# quadcopter.net
KiCad netlist of a schematic drawn in EAGLE
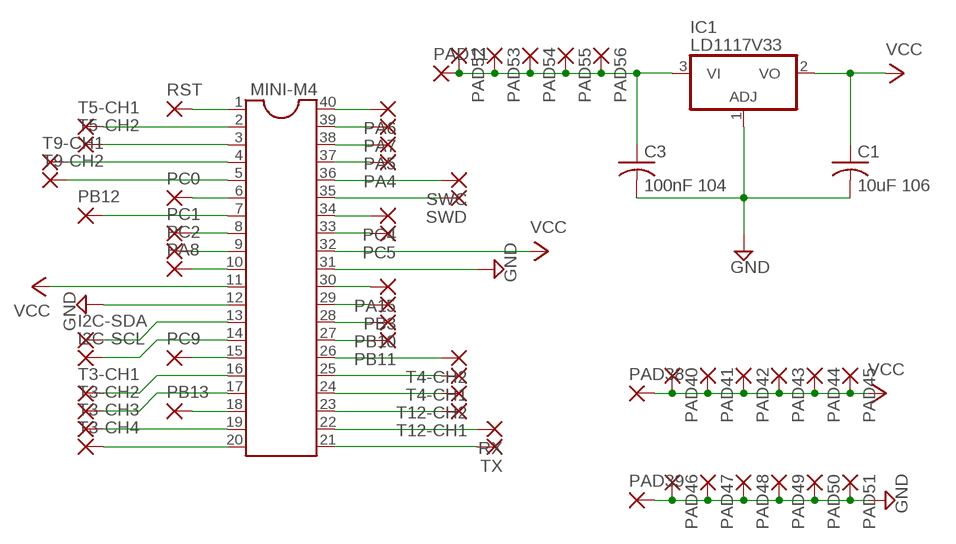
[diagram p0: schematic, sheet 1]

(export (version "E")
  (design (tool "Eeschema 10.0.6"))
  (components
    (comp (ref "C1")
      (value "10uF 106")
      (footprint "eagle-import:C025-040X050")
      (libsource (lib "eagle-import") (part "C-US025-040X050"))
    )
    (comp (ref "C3")
      (value "100nF 104")
      (footprint "eagle-import:C025-040X050")
      (libsource (lib "eagle-import") (part "C-US025-040X050"))
    )
    (comp (ref "I2C-SCL")
      (value "1,6/0,8")
      (footprint "eagle-import:1,6_0,8")
      (libsource (lib "eagle-import") (part "1,6/0,8"))
    )
    (comp (ref "I2C-SDA")
      (value "1,6/0,8")
      (footprint "eagle-import:1,6_0,8")
      (libsource (lib "eagle-import") (part "1,6/0,8"))
    )
    (comp (ref "IC1")
      (value "LD1117V33")
      (footprint "eagle-import:TO220H")
      (libsource (lib "eagle-import") (part "317T"))
    )
    (comp (ref "MINI-M4")
      (value "DIL40")
      (footprint "eagle-import:DIL40")
      (libsource (lib "eagle-import") (part "DIL40"))
    )
    (comp (ref "PA4")
      (value "1,6/0,8")
      (footprint "eagle-import:1,6_0,8")
      (libsource (lib "eagle-import") (part "1,6/0,8"))
    )
    (comp (ref "PA5")
      (value "1,6/0,8")
      (footprint "eagle-import:1,6_0,8")
      (libsource (lib "eagle-import") (part "1,6/0,8"))
    )
    (comp (ref "PA6")
      (value "1,6/0,8")
      (footprint "eagle-import:1,6_0,8")
      (libsource (lib "eagle-import") (part "1,6/0,8"))
    )
    (comp (ref "PA7")
      (value "1,6/0,8")
      (footprint "eagle-import:1,6_0,8")
      (libsource (lib "eagle-import") (part "1,6/0,8"))
    )
    (comp (ref "PA8")
      (value "1,6/0,8")
      (footprint "eagle-import:1,6_0,8")
      (libsource (lib "eagle-import") (part "1,6/0,8"))
    )
    (comp (ref "PA15")
      (value "1,6/0,8")
      (footprint "eagle-import:1,6_0,8")
      (libsource (lib "eagle-import") (part "1,6/0,8"))
    )
    (comp (ref "PAD11")
      (value "1,6/0,8")
      (footprint "eagle-import:1,6_0,8")
      (libsource (lib "eagle-import") (part "1,6/0,8"))
    )
    (comp (ref "PAD38")
      (value "1,6/0,8")
      (footprint "eagle-import:1,6_0,8")
      (libsource (lib "eagle-import") (part "1,6/0,8"))
    )
    (comp (ref "PAD39")
      (value "1,6/0,8")
      (footprint "eagle-import:1,6_0,8")
      (libsource (lib "eagle-import") (part "1,6/0,8"))
    )
    (comp (ref "PAD40")
      (value "1,6/0,8")
      (footprint "eagle-import:1,6_0,8")
      (libsource (lib "eagle-import") (part "1,6/0,8"))
    )
    (comp (ref "PAD41")
      (value "1,6/0,8")
      (footprint "eagle-import:1,6_0,8")
      (libsource (lib "eagle-import") (part "1,6/0,8"))
    )
    (comp (ref "PAD42")
      (value "1,6/0,8")
      (footprint "eagle-import:1,6_0,8")
      (libsource (lib "eagle-import") (part "1,6/0,8"))
    )
    (comp (ref "PAD43")
      (value "1,6/0,8")
      (footprint "eagle-import:1,6_0,8")
      (libsource (lib "eagle-import") (part "1,6/0,8"))
    )
    (comp (ref "PAD44")
      (value "1,6/0,8")
      (footprint "eagle-import:1,6_0,8")
      (libsource (lib "eagle-import") (part "1,6/0,8"))
    )
    (comp (ref "PAD45")
      (value "1,6/0,8")
      (footprint "eagle-import:1,6_0,8")
      (libsource (lib "eagle-import") (part "1,6/0,8"))
    )
    (comp (ref "PAD46")
      (value "1,6/0,8")
      (footprint "eagle-import:1,6_0,8")
      (libsource (lib "eagle-import") (part "1,6/0,8"))
    )
    (comp (ref "PAD47")
      (value "1,6/0,8")
      (footprint "eagle-import:1,6_0,8")
      (libsource (lib "eagle-import") (part "1,6/0,8"))
    )
    (comp (ref "PAD48")
      (value "1,6/0,8")
      (footprint "eagle-import:1,6_0,8")
      (libsource (lib "eagle-import") (part "1,6/0,8"))
    )
    (comp (ref "PAD49")
      (value "1,6/0,8")
      (footprint "eagle-import:1,6_0,8")
      (libsource (lib "eagle-import") (part "1,6/0,8"))
    )
    (comp (ref "PAD50")
      (value "1,6/0,8")
      (footprint "eagle-import:1,6_0,8")
      (libsource (lib "eagle-import") (part "1,6/0,8"))
    )
    (comp (ref "PAD51")
      (value "1,6/0,8")
      (footprint "eagle-import:1,6_0,8")
      (libsource (lib "eagle-import") (part "1,6/0,8"))
    )
    (comp (ref "PAD52")
      (value "1,6/0,8")
      (footprint "eagle-import:1,6_0,8")
      (libsource (lib "eagle-import") (part "1,6/0,8"))
    )
    (comp (ref "PAD53")
      (value "1,6/0,8")
      (footprint "eagle-import:1,6_0,8")
      (libsource (lib "eagle-import") (part "1,6/0,8"))
    )
    (comp (ref "PAD54")
      (value "1,6/0,8")
      (footprint "eagle-import:1,6_0,8")
      (libsource (lib "eagle-import") (part "1,6/0,8"))
    )
    (comp (ref "PAD55")
      (value "1,6/0,8")
      (footprint "eagle-import:1,6_0,8")
      (libsource (lib "eagle-import") (part "1,6/0,8"))
    )
    (comp (ref "PAD56")
      (value "1,6/0,8")
      (footprint "eagle-import:1,6_0,8")
      (libsource (lib "eagle-import") (part "1,6/0,8"))
    )
    (comp (ref "PB3")
      (value "1,6/0,8")
      (footprint "eagle-import:1,6_0,8")
      (libsource (lib "eagle-import") (part "1,6/0,8"))
    )
    (comp (ref "PB10")
      (value "1,6/0,8")
      (footprint "eagle-import:1,6_0,8")
      (libsource (lib "eagle-import") (part "1,6/0,8"))
    )
    (comp (ref "PB11")
      (value "1,6/0,8")
      (footprint "eagle-import:1,6_0,8")
      (libsource (lib "eagle-import") (part "1,6/0,8"))
    )
    (comp (ref "PB12")
      (value "1,6/0,8")
      (footprint "eagle-import:1,6_0,8")
      (libsource (lib "eagle-import") (part "1,6/0,8"))
    )
    (comp (ref "PB13")
      (value "1,6/0,8")
      (footprint "eagle-import:1,6_0,8")
      (libsource (lib "eagle-import") (part "1,6/0,8"))
    )
    (comp (ref "PC0")
      (value "1,6/0,8")
      (footprint "eagle-import:1,6_0,8")
      (libsource (lib "eagle-import") (part "1,6/0,8"))
    )
    (comp (ref "PC1")
      (value "1,6/0,8")
      (footprint "eagle-import:1,6_0,8")
      (libsource (lib "eagle-import") (part "1,6/0,8"))
    )
    (comp (ref "PC2")
      (value "1,6/0,8")
      (footprint "eagle-import:1,6_0,8")
      (libsource (lib "eagle-import") (part "1,6/0,8"))
    )
    (comp (ref "PC4")
      (value "1,6/0,8")
      (footprint "eagle-import:1,6_0,8")
      (libsource (lib "eagle-import") (part "1,6/0,8"))
    )
    (comp (ref "PC5")
      (value "1,6/0,8")
      (footprint "eagle-import:1,6_0,8")
      (libsource (lib "eagle-import") (part "1,6/0,8"))
    )
    (comp (ref "PC9")
      (value "1,6/0,8")
      (footprint "eagle-import:1,6_0,8")
      (libsource (lib "eagle-import") (part "1,6/0,8"))
    )
    (comp (ref "RST")
      (value "1,6/0,8")
      (footprint "eagle-import:1,6_0,8")
      (libsource (lib "eagle-import") (part "1,6/0,8"))
    )
    (comp (ref "RX")
      (value "1,6/0,8")
      (footprint "eagle-import:1,6_0,8")
      (libsource (lib "eagle-import") (part "1,6/0,8"))
    )
    (comp (ref "SWC")
      (value "1,6/0,8")
      (footprint "eagle-import:1,6_0,8")
      (libsource (lib "eagle-import") (part "1,6/0,8"))
    )
    (comp (ref "SWD")
      (value "1,6/0,8")
      (footprint "eagle-import:1,6_0,8")
      (libsource (lib "eagle-import") (part "1,6/0,8"))
    )
    (comp (ref "T3-CH1")
      (value "1,6/0,8")
      (footprint "eagle-import:1,6_0,8")
      (libsource (lib "eagle-import") (part "1,6/0,8"))
    )
    (comp (ref "T3-CH2")
      (value "1,6/0,8")
      (footprint "eagle-import:1,6_0,8")
      (libsource (lib "eagle-import") (part "1,6/0,8"))
    )
    (comp (ref "T3-CH3")
      (value "1,6/0,8")
      (footprint "eagle-import:1,6_0,8")
      (libsource (lib "eagle-import") (part "1,6/0,8"))
    )
    (comp (ref "T3-CH4")
      (value "1,6/0,8")
      (footprint "eagle-import:1,6_0,8")
      (libsource (lib "eagle-import") (part "1,6/0,8"))
    )
    (comp (ref "T4-CH1")
      (value "1,6/0,8")
      (footprint "eagle-import:1,6_0,8")
      (libsource (lib "eagle-import") (part "1,6/0,8"))
    )
    (comp (ref "T4-CH2")
      (value "1,6/0,8")
      (footprint "eagle-import:1,6_0,8")
      (libsource (lib "eagle-import") (part "1,6/0,8"))
    )
    (comp (ref "T5-CH1")
      (value "1,6/0,8")
      (footprint "eagle-import:1,6_0,8")
      (libsource (lib "eagle-import") (part "1,6/0,8"))
    )
    (comp (ref "T5-CH2")
      (value "1,6/0,8")
      (footprint "eagle-import:1,6_0,8")
      (libsource (lib "eagle-import") (part "1,6/0,8"))
    )
    (comp (ref "T9-CH1")
      (value "1,6/0,8")
      (footprint "eagle-import:1,6_0,8")
      (libsource (lib "eagle-import") (part "1,6/0,8"))
    )
    (comp (ref "T9-CH2")
      (value "1,6/0,8")
      (footprint "eagle-import:1,6_0,8")
      (libsource (lib "eagle-import") (part "1,6/0,8"))
    )
    (comp (ref "T12-CH1")
      (value "1,6/0,8")
      (footprint "eagle-import:1,6_0,8")
      (libsource (lib "eagle-import") (part "1,6/0,8"))
    )
    (comp (ref "T12-CH2")
      (value "1,6/0,8")
      (footprint "eagle-import:1,6_0,8")
      (libsource (lib "eagle-import") (part "1,6/0,8"))
    )
    (comp (ref "TX")
      (value "1,6/0,8")
      (footprint "eagle-import:1,6_0,8")
      (libsource (lib "eagle-import") (part "1,6/0,8"))
    )
  )
  (nets
    (net (code "1") (name "GND") (class "Default")
      (node (ref "C1") (pin "2") (pinfunction "2_2") (pintype "passive"))
      (node (ref "C3") (pin "2") (pinfunction "2_2") (pintype "passive"))
      (node (ref "IC1") (pin "1") (pinfunction "ADJ_1") (pintype "input"))
      (node (ref "MINI-M4") (pin "12") (pinfunction "12_12") (pintype "passive"))
      (node (ref "MINI-M4") (pin "31") (pinfunction "31_31") (pintype "passive"))
      (node (ref "PAD39") (pin "1") (pinfunction "P_1") (pintype "passive"))
      (node (ref "PAD46") (pin "1") (pinfunction "P_1") (pintype "passive"))
      (node (ref "PAD47") (pin "1") (pinfunction "P_1") (pintype "passive"))
      (node (ref "PAD48") (pin "1") (pinfunction "P_1") (pintype "passive"))
      (node (ref "PAD49") (pin "1") (pinfunction "P_1") (pintype "passive"))
      (node (ref "PAD50") (pin "1") (pinfunction "P_1") (pintype "passive"))
      (node (ref "PAD51") (pin "1") (pinfunction "P_1") (pintype "passive"))
    )
    (net (code "2") (name "Net-(I2C-SCL-P)") (class "Default")
      (node (ref "I2C-SCL") (pin "1") (pinfunction "P_1") (pintype "passive"))
      (node (ref "MINI-M4") (pin "14") (pinfunction "14_14") (pintype "passive"))
    )
    (net (code "3") (name "Net-(I2C-SDA-P)") (class "Default")
      (node (ref "I2C-SDA") (pin "1") (pinfunction "P_1") (pintype "passive"))
      (node (ref "MINI-M4") (pin "13") (pinfunction "13_13") (pintype "passive"))
    )
    (net (code "4") (name "Net-(IC1-VI)") (class "Default")
      (node (ref "C3") (pin "1") (pinfunction "1_1") (pintype "passive"))
      (node (ref "IC1") (pin "3") (pinfunction "VI_3") (pintype "input"))
      (node (ref "PAD11") (pin "1") (pinfunction "P_1") (pintype "passive"))
      (node (ref "PAD52") (pin "1") (pinfunction "P_1") (pintype "passive"))
      (node (ref "PAD53") (pin "1") (pinfunction "P_1") (pintype "passive"))
      (node (ref "PAD54") (pin "1") (pinfunction "P_1") (pintype "passive"))
      (node (ref "PAD55") (pin "1") (pinfunction "P_1") (pintype "passive"))
      (node (ref "PAD56") (pin "1") (pinfunction "P_1") (pintype "passive"))
    )
    (net (code "5") (name "Net-(PA4-P)") (class "Default")
      (node (ref "MINI-M4") (pin "37") (pinfunction "37_37") (pintype "passive"))
      (node (ref "PA4") (pin "1") (pinfunction "P_1") (pintype "passive"))
    )
    (net (code "6") (name "Net-(PA5-P)") (class "Default")
      (node (ref "MINI-M4") (pin "38") (pinfunction "38_38") (pintype "passive"))
      (node (ref "PA5") (pin "1") (pinfunction "P_1") (pintype "passive"))
    )
    (net (code "7") (name "Net-(PA6-P)") (class "Default")
      (node (ref "MINI-M4") (pin "40") (pinfunction "40_40") (pintype "passive"))
      (node (ref "PA6") (pin "1") (pinfunction "P_1") (pintype "passive"))
    )
    (net (code "8") (name "Net-(PA7-P)") (class "Default")
      (node (ref "MINI-M4") (pin "39") (pinfunction "39_39") (pintype "passive"))
      (node (ref "PA7") (pin "1") (pinfunction "P_1") (pintype "passive"))
    )
    (net (code "9") (name "Net-(PA8-P)") (class "Default")
      (node (ref "MINI-M4") (pin "10") (pinfunction "10_10") (pintype "passive"))
      (node (ref "PA8") (pin "1") (pinfunction "P_1") (pintype "passive"))
    )
    (net (code "10") (name "Net-(PA15-P)") (class "Default")
      (node (ref "MINI-M4") (pin "30") (pinfunction "30_30") (pintype "passive"))
      (node (ref "PA15") (pin "1") (pinfunction "P_1") (pintype "passive"))
    )
    (net (code "11") (name "Net-(PB3-P)") (class "Default")
      (node (ref "MINI-M4") (pin "29") (pinfunction "29_29") (pintype "passive"))
      (node (ref "PB3") (pin "1") (pinfunction "P_1") (pintype "passive"))
    )
    (net (code "12") (name "Net-(PB10-P)") (class "Default")
      (node (ref "MINI-M4") (pin "28") (pinfunction "28_28") (pintype "passive"))
      (node (ref "PB10") (pin "1") (pinfunction "P_1") (pintype "passive"))
    )
    (net (code "13") (name "Net-(PB11-P)") (class "Default")
      (node (ref "MINI-M4") (pin "27") (pinfunction "27_27") (pintype "passive"))
      (node (ref "PB11") (pin "1") (pinfunction "P_1") (pintype "passive"))
    )
    (net (code "14") (name "Net-(PB12-P)") (class "Default")
      (node (ref "MINI-M4") (pin "7") (pinfunction "7_7") (pintype "passive"))
      (node (ref "PB12") (pin "1") (pinfunction "P_1") (pintype "passive"))
    )
    (net (code "15") (name "Net-(PB13-P)") (class "Default")
      (node (ref "MINI-M4") (pin "18") (pinfunction "18_18") (pintype "passive"))
      (node (ref "PB13") (pin "1") (pinfunction "P_1") (pintype "passive"))
    )
    (net (code "16") (name "Net-(PC0-P)") (class "Default")
      (node (ref "MINI-M4") (pin "6") (pinfunction "6_6") (pintype "passive"))
      (node (ref "PC0") (pin "1") (pinfunction "P_1") (pintype "passive"))
    )
    (net (code "17") (name "Net-(PC1-P)") (class "Default")
      (node (ref "MINI-M4") (pin "8") (pinfunction "8_8") (pintype "passive"))
      (node (ref "PC1") (pin "1") (pinfunction "P_1") (pintype "passive"))
    )
    (net (code "18") (name "Net-(PC2-P)") (class "Default")
      (node (ref "MINI-M4") (pin "9") (pinfunction "9_9") (pintype "passive"))
      (node (ref "PC2") (pin "1") (pinfunction "P_1") (pintype "passive"))
    )
    (net (code "19") (name "Net-(PC4-P)") (class "Default")
      (node (ref "MINI-M4") (pin "34") (pinfunction "34_34") (pintype "passive"))
      (node (ref "PC4") (pin "1") (pinfunction "P_1") (pintype "passive"))
    )
    (net (code "20") (name "Net-(PC5-P)") (class "Default")
      (node (ref "MINI-M4") (pin "33") (pinfunction "33_33") (pintype "passive"))
      (node (ref "PC5") (pin "1") (pinfunction "P_1") (pintype "passive"))
    )
    (net (code "21") (name "Net-(PC9-P)") (class "Default")
      (node (ref "MINI-M4") (pin "15") (pinfunction "15_15") (pintype "passive"))
      (node (ref "PC9") (pin "1") (pinfunction "P_1") (pintype "passive"))
    )
    (net (code "22") (name "Net-(RST-P)") (class "Default")
      (node (ref "MINI-M4") (pin "1") (pinfunction "1_1") (pintype "passive"))
      (node (ref "RST") (pin "1") (pinfunction "P_1") (pintype "passive"))
    )
    (net (code "23") (name "Net-(RX-P)") (class "Default")
      (node (ref "MINI-M4") (pin "22") (pinfunction "22_22") (pintype "passive"))
      (node (ref "RX") (pin "1") (pinfunction "P_1") (pintype "passive"))
    )
    (net (code "24") (name "Net-(SWC-P)") (class "Default")
      (node (ref "MINI-M4") (pin "36") (pinfunction "36_36") (pintype "passive"))
      (node (ref "SWC") (pin "1") (pinfunction "P_1") (pintype "passive"))
    )
    (net (code "25") (name "Net-(SWD-P)") (class "Default")
      (node (ref "MINI-M4") (pin "35") (pinfunction "35_35") (pintype "passive"))
      (node (ref "SWD") (pin "1") (pinfunction "P_1") (pintype "passive"))
    )
    (net (code "26") (name "Net-(T3-CH1-P)") (class "Default")
      (node (ref "MINI-M4") (pin "16") (pinfunction "16_16") (pintype "passive"))
      (node (ref "T3-CH1") (pin "1") (pinfunction "P_1") (pintype "passive"))
    )
    (net (code "27") (name "Net-(T3-CH2-P)") (class "Default")
      (node (ref "MINI-M4") (pin "17") (pinfunction "17_17") (pintype "passive"))
      (node (ref "T3-CH2") (pin "1") (pinfunction "P_1") (pintype "passive"))
    )
    (net (code "28") (name "Net-(T3-CH3-P)") (class "Default")
      (node (ref "MINI-M4") (pin "19") (pinfunction "19_19") (pintype "passive"))
      (node (ref "T3-CH3") (pin "1") (pinfunction "P_1") (pintype "passive"))
    )
    (net (code "29") (name "Net-(T3-CH4-P)") (class "Default")
      (node (ref "MINI-M4") (pin "20") (pinfunction "20_20") (pintype "passive"))
      (node (ref "T3-CH4") (pin "1") (pinfunction "P_1") (pintype "passive"))
    )
    (net (code "30") (name "Net-(T4-CH1-P)") (class "Default")
      (node (ref "MINI-M4") (pin "25") (pinfunction "25_25") (pintype "passive"))
      (node (ref "T4-CH1") (pin "1") (pinfunction "P_1") (pintype "passive"))
    )
    (net (code "31") (name "Net-(T4-CH2-P)") (class "Default")
      (node (ref "MINI-M4") (pin "26") (pinfunction "26_26") (pintype "passive"))
      (node (ref "T4-CH2") (pin "1") (pinfunction "P_1") (pintype "passive"))
    )
    (net (code "32") (name "Net-(T5-CH1-P)") (class "Default")
      (node (ref "MINI-M4") (pin "2") (pinfunction "2_2") (pintype "passive"))
      (node (ref "T5-CH1") (pin "1") (pinfunction "P_1") (pintype "passive"))
    )
    (net (code "33") (name "Net-(T5-CH2-P)") (class "Default")
      (node (ref "MINI-M4") (pin "3") (pinfunction "3_3") (pintype "passive"))
      (node (ref "T5-CH2") (pin "1") (pinfunction "P_1") (pintype "passive"))
    )
    (net (code "34") (name "Net-(T9-CH1-P)") (class "Default")
      (node (ref "MINI-M4") (pin "4") (pinfunction "4_4") (pintype "passive"))
      (node (ref "T9-CH1") (pin "1") (pinfunction "P_1") (pintype "passive"))
    )
    (net (code "35") (name "Net-(T9-CH2-P)") (class "Default")
      (node (ref "MINI-M4") (pin "5") (pinfunction "5_5") (pintype "passive"))
      (node (ref "T9-CH2") (pin "1") (pinfunction "P_1") (pintype "passive"))
    )
    (net (code "36") (name "Net-(T12-CH1-P)") (class "Default")
      (node (ref "MINI-M4") (pin "23") (pinfunction "23_23") (pintype "passive"))
      (node (ref "T12-CH1") (pin "1") (pinfunction "P_1") (pintype "passive"))
    )
    (net (code "37") (name "Net-(T12-CH2-P)") (class "Default")
      (node (ref "MINI-M4") (pin "24") (pinfunction "24_24") (pintype "passive"))
      (node (ref "T12-CH2") (pin "1") (pinfunction "P_1") (pintype "passive"))
    )
    (net (code "38") (name "Net-(TX-P)") (class "Default")
      (node (ref "MINI-M4") (pin "21") (pinfunction "21_21") (pintype "passive"))
      (node (ref "TX") (pin "1") (pinfunction "P_1") (pintype "passive"))
    )
    (net (code "39") (name "VCC") (class "Default")
      (node (ref "C1") (pin "1") (pinfunction "1_1") (pintype "passive"))
      (node (ref "IC1") (pin "2") (pinfunction "VO_2") (pintype "passive"))
      (node (ref "MINI-M4") (pin "11") (pinfunction "11_11") (pintype "passive"))
      (node (ref "MINI-M4") (pin "32") (pinfunction "32_32") (pintype "passive"))
      (node (ref "PAD38") (pin "1") (pinfunction "P_1") (pintype "passive"))
      (node (ref "PAD40") (pin "1") (pinfunction "P_1") (pintype "passive"))
      (node (ref "PAD41") (pin "1") (pinfunction "P_1") (pintype "passive"))
      (node (ref "PAD42") (pin "1") (pinfunction "P_1") (pintype "passive"))
      (node (ref "PAD43") (pin "1") (pinfunction "P_1") (pintype "passive"))
      (node (ref "PAD44") (pin "1") (pinfunction "P_1") (pintype "passive"))
      (node (ref "PAD45") (pin "1") (pinfunction "P_1") (pintype "passive"))
    )
  )
)
